# NinjaPool-3J-171004.net
KiCad netlist of a schematic drawn in EAGLE
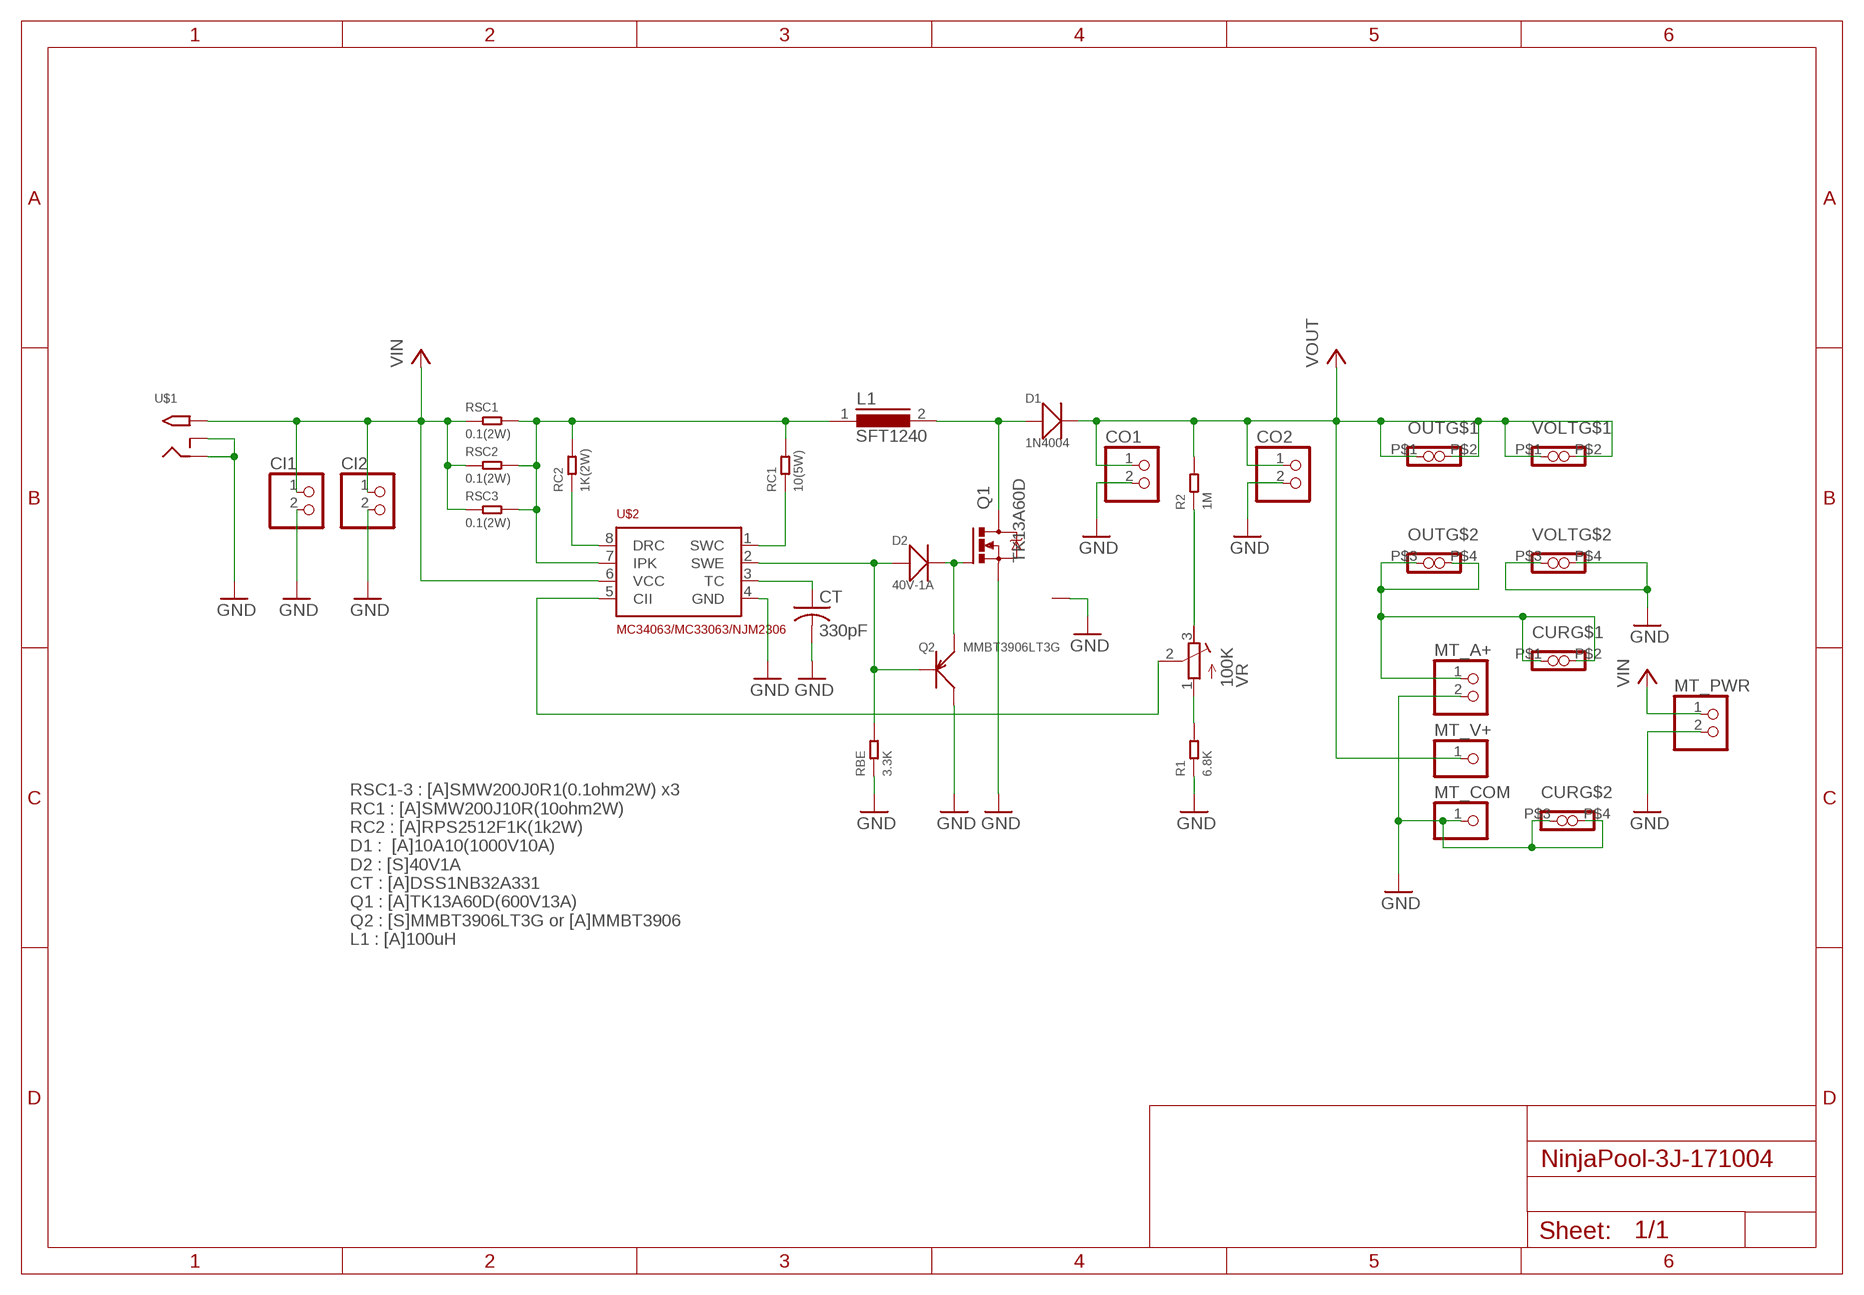
[diagram p0: schematic, sheet 1]

(export (version "E")
  (design (tool "Eeschema 10.0.6"))
  (components
    (comp (ref "CI1")
      (value "PINHD-1X2")
      (footprint "eagle-import:1X02")
      (libsource (lib "eagle-import") (part "PINHD-1X2"))
    )
    (comp (ref "CI2")
      (value "PINHD-1X2")
      (footprint "eagle-import:1X02")
      (libsource (lib "eagle-import") (part "PINHD-1X2"))
    )
    (comp (ref "CO1")
      (value "PINHD-1X2")
      (footprint "eagle-import:1X02")
      (libsource (lib "eagle-import") (part "PINHD-1X2"))
    )
    (comp (ref "CO2")
      (value "PINHD-1X2")
      (footprint "eagle-import:1X02")
      (libsource (lib "eagle-import") (part "PINHD-1X2"))
    )
    (comp (ref "CT")
      (value "330pF")
      (footprint "eagle-import:C050-024X044")
      (libsource (lib "eagle-import") (part "C-US050-024X044"))
    )
    (comp (ref "CUR")
      (value "BANANA")
      (footprint "eagle-import:BANANA_TMP")
      (libsource (lib "eagle-import") (part "BANANA"))
    )
    (comp (ref "D1")
      (value "1N4004")
      (footprint "eagle-import:DO-41")
      (libsource (lib "eagle-import") (part "DIP-DIODE-400V-1A(DO-41)"))
    )
    (comp (ref "D2")
      (value "40V-1A")
      (footprint "eagle-import:DO-214AC")
      (fields (field (name "MPN") "1N5819"))
      (libsource (lib "eagle-import") (part "SMD-DIODE-SCHOTTKY-40V-1A(DO-214AC)"))
    )
    (comp (ref "HEAT")
      (value "HEAT111PB015")
      (footprint "eagle-import:HEAT11PB015")
      (libsource (lib "eagle-import") (part "HEAT111PB015"))
    )
    (comp (ref "L1")
      (value "SFT1240")
      (footprint "eagle-import:SFT1240")
      (libsource (lib "eagle-import") (part "SFT1240"))
    )
    (comp (ref "MT_A+")
      (value "PINHD-1X2")
      (footprint "eagle-import:1X02")
      (libsource (lib "eagle-import") (part "PINHD-1X2"))
    )
    (comp (ref "MT_COM")
      (value "PINHD-1X1")
      (footprint "eagle-import:1X01")
      (libsource (lib "eagle-import") (part "PINHD-1X1"))
    )
    (comp (ref "MT_PWR")
      (value "PINHD-1X2")
      (footprint "eagle-import:1X02")
      (libsource (lib "eagle-import") (part "PINHD-1X2"))
    )
    (comp (ref "MT_V+")
      (value "PINHD-1X1")
      (footprint "eagle-import:1X01")
      (libsource (lib "eagle-import") (part "PINHD-1X1"))
    )
    (comp (ref "OUT")
      (value "BANANA")
      (footprint "eagle-import:BANANA_TMP")
      (libsource (lib "eagle-import") (part "BANANA"))
    )
    (comp (ref "Q1")
      (value "TK13A60D")
      (footprint "eagle-import:TO220BV")
      (libsource (lib "eagle-import") (part "IRF520"))
    )
    (comp (ref "Q2")
      (value "MMBT3906LT3G")
      (footprint "eagle-import:SOT-23")
      (libsource (lib "eagle-import") (part "SMD-TRANSISTORS-PNP-40V-200MA-MMBT3906LT3G(SOT-23)"))
    )
    (comp (ref "R1")
      (value "6.8K")
      (footprint "eagle-import:R0603")
      (fields (field (name "MPN") "RC0805JR-07220KL"))
      (libsource (lib "eagle-import") (part "SMD-RES-6.8K-1%-1/10W(0603)"))
    )
    (comp (ref "R2")
      (value "1M")
      (footprint "eagle-import:R0603")
      (fields (field (name "MPN") "RC0603FR-071ML"))
      (libsource (lib "eagle-import") (part "SMD-RES-1M-1%-1/10W(0603)"))
    )
    (comp (ref "RBE")
      (value "3.3K")
      (footprint "eagle-import:R0603")
      (libsource (lib "eagle-import") (part "SMD-RES-3.3K-5%-1/10W(0603)"))
    )
    (comp (ref "RC1")
      (value "10(5W)")
      (footprint "eagle-import:SWE500")
      (libsource (lib "eagle-import") (part "SWE500"))
    )
    (comp (ref "RC2")
      (value "1K(2W)")
      (footprint "eagle-import:R2512")
      (libsource (lib "eagle-import") (part "R2512"))
    )
    (comp (ref "RSC1")
      (value "0.1(2W)")
      (footprint "eagle-import:SMW200")
      (libsource (lib "eagle-import") (part "SWE200"))
    )
    (comp (ref "RSC2")
      (value "0.1(2W)")
      (footprint "eagle-import:SMW200")
      (libsource (lib "eagle-import") (part "SWE200"))
    )
    (comp (ref "RSC3")
      (value "0.1(2W)")
      (footprint "eagle-import:SMW200")
      (libsource (lib "eagle-import") (part "SWE200"))
    )
    (comp (ref "U$1")
      (value "2.1MMJACKTHM")
      (footprint "eagle-import:PJ-102A")
      (libsource (lib "eagle-import") (part "2.1MMJACKTHM"))
    )
    (comp (ref "U$2")
      (value "MC34063/MC33063/NJM2306")
      (footprint "eagle-import:DIL8")
      (libsource (lib "eagle-import") (part "MC34063/MC33063/NJM2306"))
    )
    (comp (ref "VOLT")
      (value "BANANA")
      (footprint "eagle-import:BANANA_TMP")
      (libsource (lib "eagle-import") (part "BANANA"))
    )
    (comp (ref "VR")
      (value "100K")
      (footprint "eagle-import:AITENDO_R16K1")
      (libsource (lib "eagle-import") (part "R-TRIMMAITENDO_R16K1"))
    )
  )
  (nets
    (net (code "1") (name "GND") (class "Default")
      (node (ref "CI1") (pin "2") (pinfunction "2_2") (pintype "passive"))
      (node (ref "CI2") (pin "2") (pinfunction "2_2") (pintype "passive"))
      (node (ref "CO1") (pin "2") (pinfunction "2_2") (pintype "passive"))
      (node (ref "CO2") (pin "2") (pinfunction "2_2") (pintype "passive"))
      (node (ref "CT") (pin "2") (pinfunction "2_2") (pintype "passive"))
      (node (ref "CUR") (pin "P$3") (pinfunction "1_P$3") (pintype "passive"))
      (node (ref "CUR") (pin "P$4") (pinfunction "2_P$4") (pintype "passive"))
      (node (ref "HEAT") (pin "P$1") (pinfunction "P$1_P$1") (pintype "bidirectional"))
      (node (ref "MT_A+") (pin "2") (pinfunction "2_2") (pintype "passive"))
      (node (ref "MT_COM") (pin "1") (pinfunction "1_1") (pintype "passive"))
      (node (ref "MT_PWR") (pin "2") (pinfunction "2_2") (pintype "passive"))
      (node (ref "Q1") (pin "S") (pinfunction "S_S") (pintype "passive"))
      (node (ref "Q2") (pin "3") (pinfunction "C_3") (pintype "passive"))
      (node (ref "R1") (pin "1") (pinfunction "1_1") (pintype "passive"))
      (node (ref "RBE") (pin "1") (pinfunction "1_1") (pintype "passive"))
      (node (ref "U$1") (pin "RING") (pinfunction "RING_RING") (pintype "bidirectional"))
      (node (ref "U$1") (pin "RING_SW") (pinfunction "RING_SW_RING_SW") (pintype "bidirectional"))
      (node (ref "U$2") (pin "4") (pinfunction "GND_4") (pintype "bidirectional"))
      (node (ref "VOLT") (pin "P$3") (pinfunction "1_P$3") (pintype "passive"))
      (node (ref "VOLT") (pin "P$4") (pinfunction "2_P$4") (pintype "passive"))
    )
    (net (code "2") (name "Net-(CURA-1)") (class "Default")
      (node (ref "CUR") (pin "P$1") (pinfunction "1_P$1") (pintype "passive"))
      (node (ref "CUR") (pin "P$2") (pinfunction "2_P$2") (pintype "passive"))
      (node (ref "MT_A+") (pin "1") (pinfunction "1_1") (pintype "passive"))
      (node (ref "OUT") (pin "P$3") (pinfunction "1_P$3") (pintype "passive"))
      (node (ref "OUT") (pin "P$4") (pinfunction "2_P$4") (pintype "passive"))
    )
    (net (code "3") (name "Net-(D1-+)") (class "Default")
      (node (ref "D1") (pin "1") (pinfunction "+_1") (pintype "passive"))
      (node (ref "L1") (pin "2") (pinfunction "2_2") (pintype "passive"))
      (node (ref "Q1") (pin "D") (pinfunction "D_D") (pintype "passive"))
    )
    (net (code "4") (name "Net-(D2-+)") (class "Default")
      (node (ref "D2") (pin "1") (pinfunction "+_1") (pintype "passive"))
      (node (ref "Q2") (pin "1") (pinfunction "B_1") (pintype "passive"))
      (node (ref "RBE") (pin "2") (pinfunction "2_2") (pintype "passive"))
      (node (ref "U$2") (pin "2") (pinfunction "SWE_2") (pintype "bidirectional"))
    )
    (net (code "5") (name "Net-(D2--)") (class "Default")
      (node (ref "D2") (pin "2") (pinfunction "-_2") (pintype "passive"))
      (node (ref "Q1") (pin "G") (pinfunction "G_G") (pintype "passive"))
      (node (ref "Q2") (pin "2") (pinfunction "E_2") (pintype "passive"))
    )
    (net (code "6") (name "Net-(U$2-CII)") (class "Default")
      (node (ref "U$2") (pin "5") (pinfunction "CII_5") (pintype "bidirectional"))
      (node (ref "VR") (pin "2") (pinfunction "S_2") (pintype "passive"))
    )
    (net (code "7") (name "Net-(U$2-DRC)") (class "Default")
      (node (ref "RC2") (pin "1") (pinfunction "1_1") (pintype "passive"))
      (node (ref "U$2") (pin "8") (pinfunction "DRC_8") (pintype "bidirectional"))
    )
    (net (code "8") (name "Net-(U$2-IPK)") (class "Default")
      (node (ref "L1") (pin "1") (pinfunction "1_1") (pintype "passive"))
      (node (ref "RC1") (pin "2") (pinfunction "2_2") (pintype "passive"))
      (node (ref "RC2") (pin "2") (pinfunction "2_2") (pintype "passive"))
      (node (ref "RSC1") (pin "2") (pinfunction "2_2") (pintype "passive"))
      (node (ref "RSC2") (pin "2") (pinfunction "2_2") (pintype "passive"))
      (node (ref "RSC3") (pin "2") (pinfunction "2_2") (pintype "passive"))
      (node (ref "U$2") (pin "7") (pinfunction "IPK_7") (pintype "bidirectional"))
    )
    (net (code "9") (name "Net-(U$2-SWC)") (class "Default")
      (node (ref "RC1") (pin "1") (pinfunction "1_1") (pintype "passive"))
      (node (ref "U$2") (pin "1") (pinfunction "SWC_1") (pintype "bidirectional"))
    )
    (net (code "10") (name "Net-(U$2-TC)") (class "Default")
      (node (ref "CT") (pin "1") (pinfunction "1_1") (pintype "passive"))
      (node (ref "U$2") (pin "3") (pinfunction "TC_3") (pintype "bidirectional"))
    )
    (net (code "11") (name "Net-(VR-A)") (class "Default")
      (node (ref "R1") (pin "2") (pinfunction "2_2") (pintype "passive"))
      (node (ref "VR") (pin "1") (pinfunction "A_1") (pintype "passive"))
    )
    (net (code "12") (name "Net-(VR-E)") (class "Default")
      (node (ref "R2") (pin "1") (pinfunction "1_1") (pintype "passive"))
      (node (ref "VR") (pin "3") (pinfunction "E_3") (pintype "passive"))
    )
    (net (code "13") (name "VIN") (class "Default")
      (node (ref "CI1") (pin "1") (pinfunction "1_1") (pintype "passive"))
      (node (ref "CI2") (pin "1") (pinfunction "1_1") (pintype "passive"))
      (node (ref "MT_PWR") (pin "1") (pinfunction "1_1") (pintype "passive"))
      (node (ref "RSC1") (pin "1") (pinfunction "1_1") (pintype "passive"))
      (node (ref "RSC2") (pin "1") (pinfunction "1_1") (pintype "passive"))
      (node (ref "RSC3") (pin "1") (pinfunction "1_1") (pintype "passive"))
      (node (ref "U$1") (pin "TIP") (pinfunction "TIP_TIP") (pintype "bidirectional"))
      (node (ref "U$2") (pin "6") (pinfunction "VCC_6") (pintype "bidirectional"))
    )
    (net (code "14") (name "VOUT") (class "Default")
      (node (ref "CO1") (pin "1") (pinfunction "1_1") (pintype "passive"))
      (node (ref "CO2") (pin "1") (pinfunction "1_1") (pintype "passive"))
      (node (ref "D1") (pin "2") (pinfunction "-_2") (pintype "passive"))
      (node (ref "MT_V+") (pin "1") (pinfunction "1_1") (pintype "passive"))
      (node (ref "OUT") (pin "P$1") (pinfunction "1_P$1") (pintype "passive"))
      (node (ref "OUT") (pin "P$2") (pinfunction "2_P$2") (pintype "passive"))
      (node (ref "R2") (pin "2") (pinfunction "2_2") (pintype "passive"))
      (node (ref "VOLT") (pin "P$1") (pinfunction "1_P$1") (pintype "passive"))
      (node (ref "VOLT") (pin "P$2") (pinfunction "2_P$2") (pintype "passive"))
    )
  )
)
